# SNAKE_FYP.net
KiCad netlist of a schematic drawn in Altium Designer
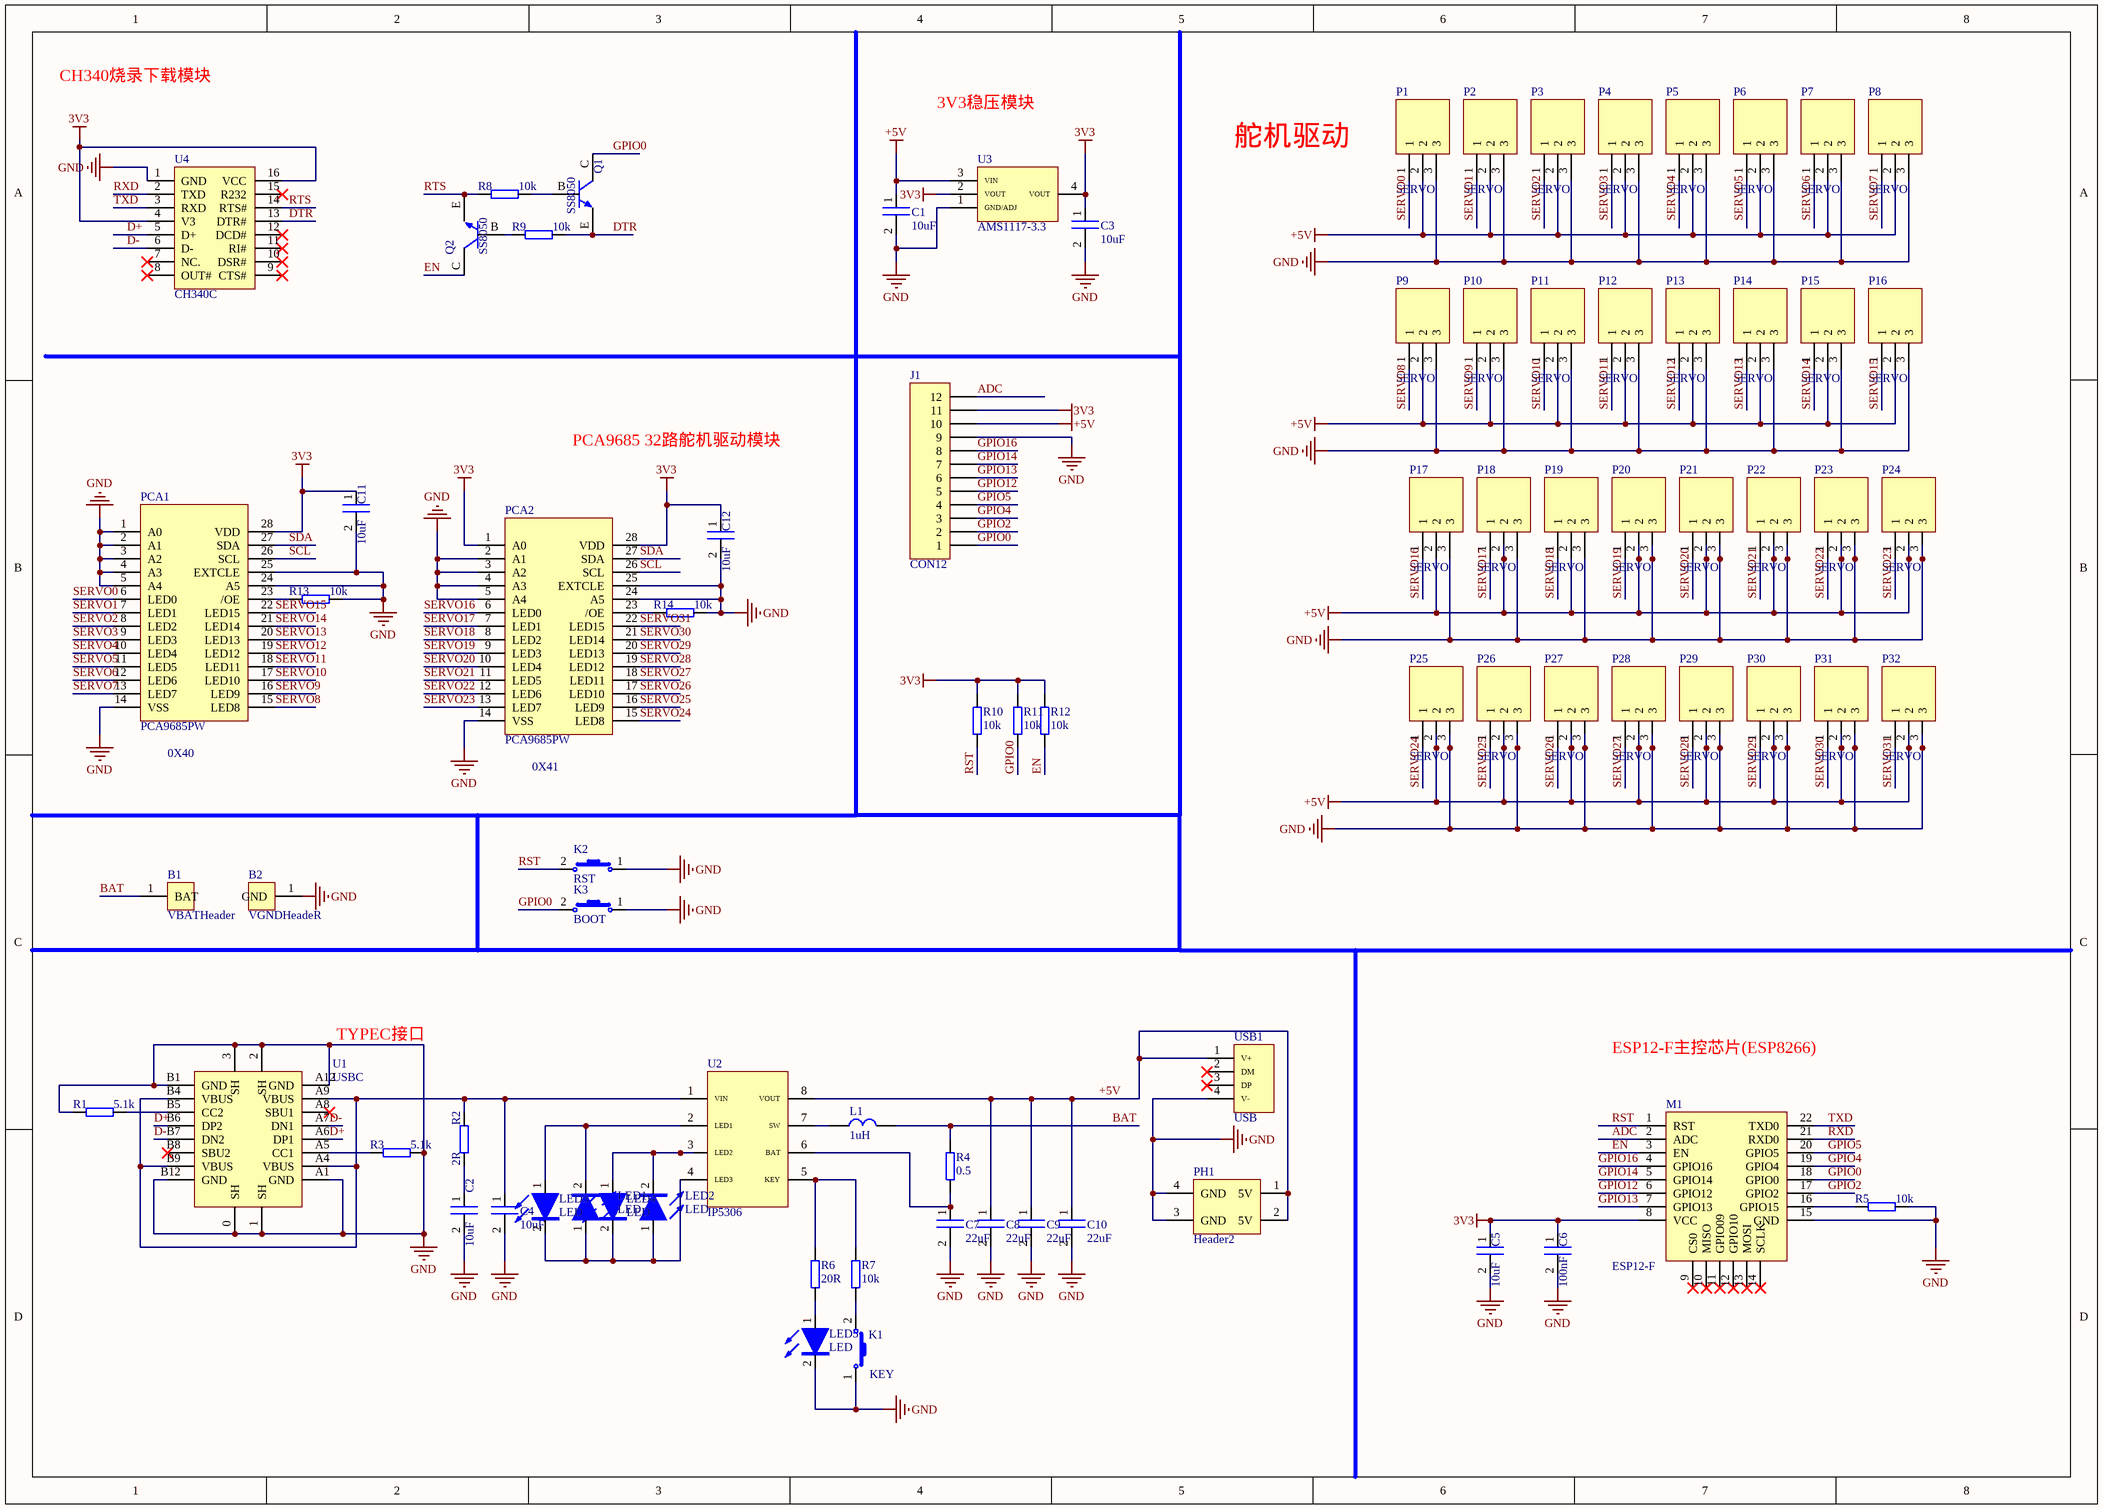
[diagram p0: SNAKE_FYP.SchDoc]

(export (version "E")
  (design (tool "Eeschema 10.0.6"))
  (components
    (comp (ref "B1")
      (value "VBATHeader")
      (footprint "18650VBAT")
      (libsource (lib "SNAKE_FYP") (part "VBATHeader"))
    )
    (comp (ref "B2")
      (value "VGNDHeadeR")
      (footprint "18650GND")
      (libsource (lib "SNAKE_FYP") (part "VGNDHeadeR"))
    )
    (comp (ref "C1")
      (value "10uF")
      (footprint "Cap-0603")
      (description "电容")
      (libsource (lib "Sc") (part "CAP"))
    )
    (comp (ref "C2")
      (value "10uF")
      (footprint "Cap-0603")
      (description "电容")
      (libsource (lib "Sc") (part "CAP"))
    )
    (comp (ref "C3")
      (value "10uF")
      (footprint "Cap-0603")
      (description "电容")
      (libsource (lib "Sc") (part "CAP"))
    )
    (comp (ref "C4")
      (value "10uF")
      (footprint "Cap-0603")
      (description "电容")
      (libsource (lib "Sc") (part "CAP"))
    )
    (comp (ref "C5")
      (value "10uF")
      (footprint "Cap-0603")
      (description "电容")
      (libsource (lib "Sc") (part "CAP"))
    )
    (comp (ref "C6")
      (value "100nF")
      (footprint "Cap-0603")
      (description "电容")
      (libsource (lib "Sc") (part "CAP"))
    )
    (comp (ref "C7")
      (value "22uF")
      (footprint "Cap-0603")
      (description "电容")
      (libsource (lib "Sc") (part "CAP"))
    )
    (comp (ref "C8")
      (value "22uF")
      (footprint "Cap-0603")
      (description "电容")
      (libsource (lib "Sc") (part "CAP"))
    )
    (comp (ref "C9")
      (value "22uF")
      (footprint "Cap-0603")
      (description "电容")
      (libsource (lib "Sc") (part "CAP"))
    )
    (comp (ref "C10")
      (value "22uF")
      (footprint "Cap-0603")
      (description "电容")
      (libsource (lib "Sc") (part "CAP"))
    )
    (comp (ref "C11")
      (value "10uF")
      (footprint "Cap-0603")
      (description "电容")
      (libsource (lib "Sc") (part "CAP"))
    )
    (comp (ref "C12")
      (value "10uF")
      (footprint "Cap-0603")
      (description "电容")
      (libsource (lib "Sc") (part "CAP"))
    )
    (comp (ref "J1")
      (value "CON12")
      (footprint "HDR2X6")
      (description "Connector")
      (libsource (lib "Sc") (part "CON12"))
    )
    (comp (ref "K1")
      (value "KEY")
      (footprint "TSW SMD-3*6*2.5(Button)")
      (description "按键")
      (libsource (lib "Hexapod") (part "RST"))
    )
    (comp (ref "K2")
      (value "RST")
      (footprint "TSW SMD-3*6*2.5(Button)")
      (description "按键")
      (libsource (lib "Sc") (part "RST"))
    )
    (comp (ref "K3")
      (value "BOOT")
      (footprint "TSW SMD-3*6*2.5(Button)")
      (description "按键")
      (libsource (lib "Sc") (part "RST"))
    )
    (comp (ref "L1")
      (value "1uH")
      (footprint "CDRH3D16_4.2*1.8")
      (description "电感")
      (libsource (lib "Hexapod") (part "INDUCTOR"))
    )
    (comp (ref "LED1") (value "LED") (footprint "LED-0805") (libsource (lib "Hexapod") (part "LED")))
    (comp (ref "LED2") (value "LED") (footprint "LED-0805") (libsource (lib "Hexapod") (part "LED")))
    (comp (ref "LED3") (value "LED") (footprint "LED-0805") (libsource (lib "Hexapod") (part "LED")))
    (comp (ref "LED4") (value "LED") (footprint "LED-0805") (libsource (lib "Hexapod") (part "LED")))
    (comp (ref "LED5") (value "LED") (footprint "LED-0805") (libsource (lib "Hexapod") (part "LED")))
    (comp (ref "M1") (value "ESP12-F") (footprint "ESP-12F") (libsource (lib "Sc") (part "ESP12-F")))
    (comp (ref "P1") (value "SERVO") (footprint "SERVOHEADER") (libsource (lib "Sc") (part "SERVO")))
    (comp (ref "P2") (value "SERVO") (footprint "SERVOHEADER") (libsource (lib "Sc") (part "SERVO")))
    (comp (ref "P3") (value "SERVO") (footprint "SERVOHEADER") (libsource (lib "Sc") (part "SERVO")))
    (comp (ref "P4") (value "SERVO") (footprint "SERVOHEADER") (libsource (lib "Sc") (part "SERVO")))
    (comp (ref "P5") (value "SERVO") (footprint "SERVOHEADER") (libsource (lib "Sc") (part "SERVO")))
    (comp (ref "P6") (value "SERVO") (footprint "SERVOHEADER") (libsource (lib "Sc") (part "SERVO")))
    (comp (ref "P7") (value "SERVO") (footprint "SERVOHEADER") (libsource (lib "Sc") (part "SERVO")))
    (comp (ref "P8") (value "SERVO") (footprint "SERVOHEADER") (libsource (lib "Sc") (part "SERVO")))
    (comp (ref "P9") (value "SERVO") (footprint "SERVOHEADER") (libsource (lib "Sc") (part "SERVO")))
    (comp (ref "P10") (value "SERVO") (footprint "SERVOHEADER") (libsource (lib "Sc") (part "SERVO")))
    (comp (ref "P11") (value "SERVO") (footprint "SERVOHEADER") (libsource (lib "Sc") (part "SERVO")))
    (comp (ref "P12") (value "SERVO") (footprint "SERVOHEADER") (libsource (lib "Sc") (part "SERVO")))
    (comp (ref "P13") (value "SERVO") (footprint "SERVOHEADER") (libsource (lib "Sc") (part "SERVO")))
    (comp (ref "P14") (value "SERVO") (footprint "SERVOHEADER") (libsource (lib "Sc") (part "SERVO")))
    (comp (ref "P15") (value "SERVO") (footprint "SERVOHEADER") (libsource (lib "Sc") (part "SERVO")))
    (comp (ref "P16") (value "SERVO") (footprint "SERVOHEADER") (libsource (lib "Sc") (part "SERVO")))
    (comp (ref "P17") (value "SERVO") (footprint "SERVOHEADER") (libsource (lib "Sc") (part "SERVO")))
    (comp (ref "P18") (value "SERVO") (footprint "SERVOHEADER") (libsource (lib "Sc") (part "SERVO")))
    (comp (ref "P19") (value "SERVO") (footprint "SERVOHEADER") (libsource (lib "Sc") (part "SERVO")))
    (comp (ref "P20") (value "SERVO") (footprint "SERVOHEADER") (libsource (lib "Sc") (part "SERVO")))
    (comp (ref "P21") (value "SERVO") (footprint "SERVOHEADER") (libsource (lib "Sc") (part "SERVO")))
    (comp (ref "P22") (value "SERVO") (footprint "SERVOHEADER") (libsource (lib "Sc") (part "SERVO")))
    (comp (ref "P23") (value "SERVO") (footprint "SERVOHEADER") (libsource (lib "Sc") (part "SERVO")))
    (comp (ref "P24") (value "SERVO") (footprint "SERVOHEADER") (libsource (lib "Sc") (part "SERVO")))
    (comp (ref "P25") (value "SERVO") (footprint "SERVOHEADER") (libsource (lib "Sc") (part "SERVO")))
    (comp (ref "P26") (value "SERVO") (footprint "SERVOHEADER") (libsource (lib "Sc") (part "SERVO")))
    (comp (ref "P27") (value "SERVO") (footprint "SERVOHEADER") (libsource (lib "Sc") (part "SERVO")))
    (comp (ref "P28") (value "SERVO") (footprint "SERVOHEADER") (libsource (lib "Sc") (part "SERVO")))
    (comp (ref "P29") (value "SERVO") (footprint "SERVOHEADER") (libsource (lib "Sc") (part "SERVO")))
    (comp (ref "P30") (value "SERVO") (footprint "SERVOHEADER") (libsource (lib "Sc") (part "SERVO")))
    (comp (ref "P31") (value "SERVO") (footprint "SERVOHEADER") (libsource (lib "Sc") (part "SERVO")))
    (comp (ref "P32") (value "SERVO") (footprint "SERVOHEADER") (libsource (lib "Sc") (part "SERVO")))
    (comp (ref "PCA1")
      (value "PCA9685PW")
      (footprint "PCA9685TSOP28")
      (libsource (lib "Sc") (part "PCA9685PW"))
    )
    (comp (ref "PCA2")
      (value "PCA9685PW")
      (footprint "PCA9685TSOP28")
      (libsource (lib "Sc") (part "PCA9685PW"))
    )
    (comp (ref "PH1") (value "Header2") (footprint "HDR2X2") (libsource (lib "ip5306pw") (part "Header2")))
    (comp (ref "Q1") (value "SS8050") (footprint "SOT-23_BEC(SS8050)") (libsource (lib "Sc") (part "SS8050")))
    (comp (ref "Q2") (value "SS8050") (footprint "SOT-23_BEC(SS8050)") (libsource (lib "Sc") (part "SS8050")))
    (comp (ref "R1")
      (value "5.1k")
      (footprint "0603_RES")
      (description "电阻")
      (libsource (lib "Sc") (part "RES"))
    )
    (comp (ref "R2")
      (value "2R")
      (footprint "0603_RES")
      (description "电阻")
      (libsource (lib "Hexapod") (part "RES"))
    )
    (comp (ref "R3")
      (value "5.1k")
      (footprint "0603_RES")
      (description "电阻")
      (libsource (lib "Sc") (part "RES"))
    )
    (comp (ref "R4")
      (value "0.5")
      (footprint "0603_RES")
      (description "电阻")
      (libsource (lib "Hexapod") (part "RES"))
    )
    (comp (ref "R5")
      (value "10k")
      (footprint "0603_RES")
      (description "电阻")
      (libsource (lib "Sc") (part "RES"))
    )
    (comp (ref "R6")
      (value "20R")
      (footprint "0603_RES")
      (description "电阻")
      (libsource (lib "Hexapod") (part "RES"))
    )
    (comp (ref "R7")
      (value "10k")
      (footprint "0603_RES")
      (description "电阻")
      (libsource (lib "Hexapod") (part "RES"))
    )
    (comp (ref "R8")
      (value "10k")
      (footprint "0603_RES")
      (description "电阻")
      (libsource (lib "Sc") (part "RES"))
    )
    (comp (ref "R9")
      (value "10k")
      (footprint "0603_RES")
      (description "电阻")
      (libsource (lib "Sc") (part "RES"))
    )
    (comp (ref "R10")
      (value "10k")
      (footprint "0603_RES")
      (description "电阻")
      (libsource (lib "Sc") (part "RES"))
    )
    (comp (ref "R11")
      (value "10k")
      (footprint "0603_RES")
      (description "电阻")
      (libsource (lib "Sc") (part "RES"))
    )
    (comp (ref "R12")
      (value "10k")
      (footprint "0603_RES")
      (description "电阻")
      (libsource (lib "Sc") (part "RES"))
    )
    (comp (ref "R13")
      (value "10k")
      (footprint "0603_RES")
      (description "电阻")
      (libsource (lib "Sc") (part "RES"))
    )
    (comp (ref "R14")
      (value "10k")
      (footprint "0603_RES")
      (description "电阻")
      (libsource (lib "Sc") (part "RES"))
    )
    (comp (ref "U1") (value "USBC") (footprint "TYPEC") (libsource (lib "ip5306pw") (part "USBC")))
    (comp (ref "U2")
      (value "IP5306")
      (footprint "ESOP_IP5306")
      (description "升压、降压和锂电池充电管理芯片")
      (libsource (lib "ip5306pw") (part "IP5306"))
    )
    (comp (ref "U3")
      (value "AMS1117-3.3")
      (footprint "SOT229P700X180-4N(AMS1117-3.3)")
      (libsource (lib "Sc") (part "AMS1117-3.3"))
    )
    (comp (ref "U4") (value "CH340C") (footprint "SO016_CH340") (libsource (lib "Sc") (part "CH340")))
    (comp (ref "USB1") (value "USB") (footprint "TypeA") (libsource (lib "ip5306pw") (part "USB")))
  )
  (nets
    (net (code "1") (name "+5V") (class "Default")
      (node (ref "C1") (pin "1") (pinfunction "1_1") (pintype "passive"))
      (node (ref "C10") (pin "1") (pinfunction "1_1") (pintype "passive"))
      (node (ref "C8") (pin "1") (pinfunction "1_1") (pintype "passive"))
      (node (ref "C9") (pin "1") (pinfunction "1_1") (pintype "passive"))
      (node (ref "J1") (pin "10") (pinfunction "10_10") (pintype "passive"))
      (node (ref "P1") (pin "2") (pinfunction "2_2") (pintype "passive"))
      (node (ref "P10") (pin "2") (pinfunction "2_2") (pintype "passive"))
      (node (ref "P11") (pin "2") (pinfunction "2_2") (pintype "passive"))
      (node (ref "P12") (pin "2") (pinfunction "2_2") (pintype "passive"))
      (node (ref "P13") (pin "2") (pinfunction "2_2") (pintype "passive"))
      (node (ref "P14") (pin "2") (pinfunction "2_2") (pintype "passive"))
      (node (ref "P15") (pin "2") (pinfunction "2_2") (pintype "passive"))
      (node (ref "P16") (pin "2") (pinfunction "2_2") (pintype "passive"))
      (node (ref "P17") (pin "2") (pinfunction "2_2") (pintype "passive"))
      (node (ref "P18") (pin "2") (pinfunction "2_2") (pintype "passive"))
      (node (ref "P19") (pin "2") (pinfunction "2_2") (pintype "passive"))
      (node (ref "P2") (pin "2") (pinfunction "2_2") (pintype "passive"))
      (node (ref "P20") (pin "2") (pinfunction "2_2") (pintype "passive"))
      (node (ref "P21") (pin "2") (pinfunction "2_2") (pintype "passive"))
      (node (ref "P22") (pin "2") (pinfunction "2_2") (pintype "passive"))
      (node (ref "P23") (pin "2") (pinfunction "2_2") (pintype "passive"))
      (node (ref "P24") (pin "2") (pinfunction "2_2") (pintype "passive"))
      (node (ref "P25") (pin "2") (pinfunction "2_2") (pintype "passive"))
      (node (ref "P26") (pin "2") (pinfunction "2_2") (pintype "passive"))
      (node (ref "P27") (pin "2") (pinfunction "2_2") (pintype "passive"))
      (node (ref "P28") (pin "2") (pinfunction "2_2") (pintype "passive"))
      (node (ref "P29") (pin "2") (pinfunction "2_2") (pintype "passive"))
      (node (ref "P3") (pin "2") (pinfunction "2_2") (pintype "passive"))
      (node (ref "P30") (pin "2") (pinfunction "2_2") (pintype "passive"))
      (node (ref "P31") (pin "2") (pinfunction "2_2") (pintype "passive"))
      (node (ref "P32") (pin "2") (pinfunction "2_2") (pintype "passive"))
      (node (ref "P4") (pin "2") (pinfunction "2_2") (pintype "passive"))
      (node (ref "P5") (pin "2") (pinfunction "2_2") (pintype "passive"))
      (node (ref "P6") (pin "2") (pinfunction "2_2") (pintype "passive"))
      (node (ref "P7") (pin "2") (pinfunction "2_2") (pintype "passive"))
      (node (ref "P8") (pin "2") (pinfunction "2_2") (pintype "passive"))
      (node (ref "P9") (pin "2") (pinfunction "2_2") (pintype "passive"))
      (node (ref "PH1") (pin "1") (pinfunction "5V_1") (pintype "passive"))
      (node (ref "PH1") (pin "2") (pinfunction "5V_2") (pintype "passive"))
      (node (ref "U2") (pin "8") (pinfunction "VOUT_8") (pintype "passive"))
      (node (ref "U3") (pin "3") (pinfunction "VIN_3") (pintype "passive"))
      (node (ref "USB1") (pin "1") (pinfunction "V+_1") (pintype "passive"))
    )
    (net (code "2") (name "/ADC") (class "Default")
      (node (ref "J1") (pin "12") (pinfunction "12_12") (pintype "passive"))
      (node (ref "M1") (pin "2") (pinfunction "ADC_2") (pintype "passive"))
    )
    (net (code "3") (name "/BAT") (class "Default")
      (node (ref "B1") (pin "1") (pinfunction "BAT_1") (pintype "passive"))
      (node (ref "L1") (pin "2") (pinfunction "2_2") (pintype "passive"))
      (node (ref "R4") (pin "2") (pinfunction "2_2") (pintype "passive"))
    )
    (net (code "4") (name "/D+") (class "Default")
      (node (ref "U1") (pin "A6") (pinfunction "DP1_A6") (pintype "passive"))
      (node (ref "U1") (pin "B6") (pinfunction "DP2_B6") (pintype "passive"))
      (node (ref "U4") (pin "5") (pinfunction "D+_5") (pintype "passive"))
    )
    (net (code "5") (name "/D-") (class "Default")
      (node (ref "U1") (pin "A7") (pinfunction "DN1_A7") (pintype "passive"))
      (node (ref "U1") (pin "B7") (pinfunction "DN2_B7") (pintype "passive"))
      (node (ref "U4") (pin "6") (pinfunction "D-_6") (pintype "passive"))
    )
    (net (code "6") (name "/DTR") (class "Default")
      (node (ref "Q1") (pin "E") (pinfunction "3_E") (pintype "passive"))
      (node (ref "R9") (pin "2") (pinfunction "2_2") (pintype "passive"))
      (node (ref "U4") (pin "13") (pinfunction "DTR#_13") (pintype "passive"))
    )
    (net (code "7") (name "/EN") (class "Default")
      (node (ref "M1") (pin "3") (pinfunction "EN_3") (pintype "passive"))
      (node (ref "Q2") (pin "C") (pinfunction "1_C") (pintype "passive"))
      (node (ref "R12") (pin "2") (pinfunction "2_2") (pintype "passive"))
    )
    (net (code "8") (name "/GPIO0") (class "Default")
      (node (ref "J1") (pin "1") (pinfunction "1_1") (pintype "passive"))
      (node (ref "K3") (pin "2") (pinfunction "2_2") (pintype "passive"))
      (node (ref "M1") (pin "18") (pinfunction "GPIO0_18") (pintype "passive"))
      (node (ref "Q1") (pin "C") (pinfunction "1_C") (pintype "passive"))
      (node (ref "R11") (pin "2") (pinfunction "2_2") (pintype "passive"))
    )
    (net (code "9") (name "/GPIO2") (class "Default")
      (node (ref "J1") (pin "2") (pinfunction "2_2") (pintype "passive"))
      (node (ref "M1") (pin "17") (pinfunction "GPIO2_17") (pintype "passive"))
    )
    (net (code "10") (name "/GPIO4") (class "Default")
      (node (ref "J1") (pin "3") (pinfunction "3_3") (pintype "passive"))
      (node (ref "M1") (pin "19") (pinfunction "GPIO4_19") (pintype "passive"))
    )
    (net (code "11") (name "/GPIO5") (class "Default")
      (node (ref "J1") (pin "4") (pinfunction "4_4") (pintype "passive"))
      (node (ref "M1") (pin "20") (pinfunction "GPIO5_20") (pintype "passive"))
    )
    (net (code "12") (name "/GPIO12") (class "Default")
      (node (ref "J1") (pin "5") (pinfunction "5_5") (pintype "passive"))
      (node (ref "M1") (pin "6") (pinfunction "GPIO12_6") (pintype "passive"))
    )
    (net (code "13") (name "/GPIO13") (class "Default")
      (node (ref "J1") (pin "6") (pinfunction "6_6") (pintype "passive"))
      (node (ref "M1") (pin "7") (pinfunction "GPIO13_7") (pintype "passive"))
    )
    (net (code "14") (name "/GPIO14") (class "Default")
      (node (ref "J1") (pin "7") (pinfunction "7_7") (pintype "passive"))
      (node (ref "M1") (pin "5") (pinfunction "GPIO14_5") (pintype "passive"))
    )
    (net (code "15") (name "/GPIO16") (class "Default")
      (node (ref "J1") (pin "8") (pinfunction "8_8") (pintype "passive"))
      (node (ref "M1") (pin "4") (pinfunction "GPIO16_4") (pintype "passive"))
    )
    (net (code "16") (name "/RST") (class "Default")
      (node (ref "K2") (pin "2") (pinfunction "2_2") (pintype "passive"))
      (node (ref "M1") (pin "1") (pinfunction "RST_1") (pintype "passive"))
      (node (ref "R10") (pin "2") (pinfunction "2_2") (pintype "passive"))
    )
    (net (code "17") (name "/RTS") (class "Default")
      (node (ref "Q2") (pin "E") (pinfunction "3_E") (pintype "passive"))
      (node (ref "R8") (pin "1") (pinfunction "1_1") (pintype "passive"))
      (node (ref "U4") (pin "14") (pinfunction "RTS#_14") (pintype "passive"))
    )
    (net (code "18") (name "/RXD") (class "Default")
      (node (ref "M1") (pin "21") (pinfunction "RXD0_21") (pintype "passive"))
      (node (ref "U4") (pin "2") (pinfunction "TXD_2") (pintype "passive"))
    )
    (net (code "19") (name "/SCL") (class "Default")
      (node (ref "PCA1") (pin "26") (pinfunction "SCL_26") (pintype "passive"))
      (node (ref "PCA2") (pin "26") (pinfunction "SCL_26") (pintype "passive"))
    )
    (net (code "20") (name "/SDA") (class "Default")
      (node (ref "PCA1") (pin "27") (pinfunction "SDA_27") (pintype "passive"))
      (node (ref "PCA2") (pin "27") (pinfunction "SDA_27") (pintype "passive"))
    )
    (net (code "21") (name "/SERVO0") (class "Default")
      (node (ref "P1") (pin "1") (pinfunction "1_1") (pintype "passive"))
      (node (ref "PCA1") (pin "6") (pinfunction "LED0_6") (pintype "passive"))
    )
    (net (code "22") (name "/SERVO1") (class "Default")
      (node (ref "P2") (pin "1") (pinfunction "1_1") (pintype "passive"))
      (node (ref "PCA1") (pin "7") (pinfunction "LED1_7") (pintype "passive"))
    )
    (net (code "23") (name "/SERVO2") (class "Default")
      (node (ref "P3") (pin "1") (pinfunction "1_1") (pintype "passive"))
      (node (ref "PCA1") (pin "8") (pinfunction "LED2_8") (pintype "passive"))
    )
    (net (code "24") (name "/SERVO3") (class "Default")
      (node (ref "P4") (pin "1") (pinfunction "1_1") (pintype "passive"))
      (node (ref "PCA1") (pin "9") (pinfunction "LED3_9") (pintype "passive"))
    )
    (net (code "25") (name "/SERVO4") (class "Default")
      (node (ref "P5") (pin "1") (pinfunction "1_1") (pintype "passive"))
      (node (ref "PCA1") (pin "10") (pinfunction "LED4_10") (pintype "passive"))
    )
    (net (code "26") (name "/SERVO5") (class "Default")
      (node (ref "P6") (pin "1") (pinfunction "1_1") (pintype "passive"))
      (node (ref "PCA1") (pin "11") (pinfunction "LED5_11") (pintype "passive"))
    )
    (net (code "27") (name "/SERVO6") (class "Default")
      (node (ref "P7") (pin "1") (pinfunction "1_1") (pintype "passive"))
      (node (ref "PCA1") (pin "12") (pinfunction "LED6_12") (pintype "passive"))
    )
    (net (code "28") (name "/SERVO7") (class "Default")
      (node (ref "P8") (pin "1") (pinfunction "1_1") (pintype "passive"))
      (node (ref "PCA1") (pin "13") (pinfunction "LED7_13") (pintype "passive"))
    )
    (net (code "29") (name "/SERVO8") (class "Default")
      (node (ref "P9") (pin "1") (pinfunction "1_1") (pintype "passive"))
      (node (ref "PCA1") (pin "15") (pinfunction "LED8_15") (pintype "passive"))
    )
    (net (code "30") (name "/SERVO9") (class "Default")
      (node (ref "P10") (pin "1") (pinfunction "1_1") (pintype "passive"))
      (node (ref "PCA1") (pin "16") (pinfunction "LED9_16") (pintype "passive"))
    )
    (net (code "31") (name "/SERVO10") (class "Default")
      (node (ref "P11") (pin "1") (pinfunction "1_1") (pintype "passive"))
      (node (ref "PCA1") (pin "17") (pinfunction "LED10_17") (pintype "passive"))
    )
    (net (code "32") (name "/SERVO11") (class "Default")
      (node (ref "P12") (pin "1") (pinfunction "1_1") (pintype "passive"))
      (node (ref "PCA1") (pin "18") (pinfunction "LED11_18") (pintype "passive"))
    )
    (net (code "33") (name "/SERVO12") (class "Default")
      (node (ref "P13") (pin "1") (pinfunction "1_1") (pintype "passive"))
      (node (ref "PCA1") (pin "19") (pinfunction "LED12_19") (pintype "passive"))
    )
    (net (code "34") (name "/SERVO13") (class "Default")
      (node (ref "P14") (pin "1") (pinfunction "1_1") (pintype "passive"))
      (node (ref "PCA1") (pin "20") (pinfunction "LED13_20") (pintype "passive"))
    )
    (net (code "35") (name "/SERVO14") (class "Default")
      (node (ref "P15") (pin "1") (pinfunction "1_1") (pintype "passive"))
      (node (ref "PCA1") (pin "21") (pinfunction "LED14_21") (pintype "passive"))
    )
    (net (code "36") (name "/SERVO15") (class "Default")
      (node (ref "P16") (pin "1") (pinfunction "1_1") (pintype "passive"))
      (node (ref "PCA1") (pin "22") (pinfunction "LED15_22") (pintype "passive"))
    )
    (net (code "37") (name "/SERVO16") (class "Default")
      (node (ref "P17") (pin "1") (pinfunction "1_1") (pintype "passive"))
      (node (ref "PCA2") (pin "6") (pinfunction "LED0_6") (pintype "passive"))
    )
    (net (code "38") (name "/SERVO17") (class "Default")
      (node (ref "P18") (pin "1") (pinfunction "1_1") (pintype "passive"))
      (node (ref "PCA2") (pin "7") (pinfunction "LED1_7") (pintype "passive"))
    )
    (net (code "39") (name "/SERVO18") (class "Default")
      (node (ref "P19") (pin "1") (pinfunction "1_1") (pintype "passive"))
      (node (ref "PCA2") (pin "8") (pinfunction "LED2_8") (pintype "passive"))
    )
    (net (code "40") (name "/SERVO19") (class "Default")
      (node (ref "P20") (pin "1") (pinfunction "1_1") (pintype "passive"))
      (node (ref "PCA2") (pin "9") (pinfunction "LED3_9") (pintype "passive"))
    )
    (net (code "41") (name "/SERVO20") (class "Default")
      (node (ref "P21") (pin "1") (pinfunction "1_1") (pintype "passive"))
      (node (ref "PCA2") (pin "10") (pinfunction "LED4_10") (pintype "passive"))
    )
    (net (code "42") (name "/SERVO21") (class "Default")
      (node (ref "P22") (pin "1") (pinfunction "1_1") (pintype "passive"))
      (node (ref "PCA2") (pin "11") (pinfunction "LED5_11") (pintype "passive"))
    )
    (net (code "43") (name "/SERVO22") (class "Default")
      (node (ref "P23") (pin "1") (pinfunction "1_1") (pintype "passive"))
      (node (ref "PCA2") (pin "12") (pinfunction "LED6_12") (pintype "passive"))
    )
    (net (code "44") (name "/SERVO23") (class "Default")
      (node (ref "P24") (pin "1") (pinfunction "1_1") (pintype "passive"))
      (node (ref "PCA2") (pin "13") (pinfunction "LED7_13") (pintype "passive"))
    )
    (net (code "45") (name "/SERVO24") (class "Default")
      (node (ref "P25") (pin "1") (pinfunction "1_1") (pintype "passive"))
      (node (ref "PCA2") (pin "15") (pinfunction "LED8_15") (pintype "passive"))
    )
    (net (code "46") (name "/SERVO25") (class "Default")
      (node (ref "P26") (pin "1") (pinfunction "1_1") (pintype "passive"))
      (node (ref "PCA2") (pin "16") (pinfunction "LED9_16") (pintype "passive"))
    )
    (net (code "47") (name "/SERVO26") (class "Default")
      (node (ref "P27") (pin "1") (pinfunction "1_1") (pintype "passive"))
      (node (ref "PCA2") (pin "17") (pinfunction "LED10_17") (pintype "passive"))
    )
    (net (code "48") (name "/SERVO27") (class "Default")
      (node (ref "P28") (pin "1") (pinfunction "1_1") (pintype "passive"))
      (node (ref "PCA2") (pin "18") (pinfunction "LED11_18") (pintype "passive"))
    )
    (net (code "49") (name "/SERVO28") (class "Default")
      (node (ref "P29") (pin "1") (pinfunction "1_1") (pintype "passive"))
      (node (ref "PCA2") (pin "19") (pinfunction "LED12_19") (pintype "passive"))
    )
    (net (code "50") (name "/SERVO29") (class "Default")
      (node (ref "P30") (pin "1") (pinfunction "1_1") (pintype "passive"))
      (node (ref "PCA2") (pin "20") (pinfunction "LED13_20") (pintype "passive"))
    )
    (net (code "51") (name "/SERVO30") (class "Default")
      (node (ref "P31") (pin "1") (pinfunction "1_1") (pintype "passive"))
      (node (ref "PCA2") (pin "21") (pinfunction "LED14_21") (pintype "passive"))
    )
    (net (code "52") (name "/SERVO31") (class "Default")
      (node (ref "P32") (pin "1") (pinfunction "1_1") (pintype "passive"))
      (node (ref "PCA2") (pin "22") (pinfunction "LED15_22") (pintype "passive"))
    )
    (net (code "53") (name "/TXD") (class "Default")
      (node (ref "M1") (pin "22") (pinfunction "TXD0_22") (pintype "passive"))
      (node (ref "U4") (pin "3") (pinfunction "RXD_3") (pintype "passive"))
    )
    (net (code "54") (name "3V3") (class "Default")
      (node (ref "C11") (pin "1") (pinfunction "1_1") (pintype "passive"))
      (node (ref "C12") (pin "1") (pinfunction "1_1") (pintype "passive"))
      (node (ref "C3") (pin "1") (pinfunction "1_1") (pintype "passive"))
      (node (ref "C5") (pin "1") (pinfunction "1_1") (pintype "passive"))
      (node (ref "C6") (pin "1") (pinfunction "1_1") (pintype "passive"))
      (node (ref "J1") (pin "11") (pinfunction "11_11") (pintype "passive"))
      (node (ref "M1") (pin "8") (pinfunction "VCC_8") (pintype "passive"))
      (node (ref "PCA1") (pin "28") (pinfunction "VDD_28") (pintype "passive"))
      (node (ref "PCA2") (pin "1") (pinfunction "A0_1") (pintype "passive"))
      (node (ref "PCA2") (pin "28") (pinfunction "VDD_28") (pintype "passive"))
      (node (ref "R10") (pin "1") (pinfunction "1_1") (pintype "passive"))
      (node (ref "R11") (pin "1") (pinfunction "1_1") (pintype "passive"))
      (node (ref "R12") (pin "1") (pinfunction "1_1") (pintype "passive"))
      (node (ref "U3") (pin "2") (pinfunction "VOUT_2") (pintype "passive"))
      (node (ref "U3") (pin "4") (pinfunction "VOUT_4") (pintype "passive"))
      (node (ref "U4") (pin "16") (pinfunction "VCC_16") (pintype "passive"))
      (node (ref "U4") (pin "4") (pinfunction "V3_4") (pintype "passive"))
    )
    (net (code "55") (name "GND") (class "Default")
      (node (ref "B2") (pin "1") (pinfunction "GND_1") (pintype "passive"))
      (node (ref "C1") (pin "2") (pinfunction "2_2") (pintype "passive"))
      (node (ref "C10") (pin "2") (pinfunction "2_2") (pintype "passive"))
      (node (ref "C11") (pin "2") (pinfunction "2_2") (pintype "passive"))
      (node (ref "C12") (pin "2") (pinfunction "2_2") (pintype "passive"))
      (node (ref "C2") (pin "2") (pinfunction "2_2") (pintype "passive"))
      (node (ref "C3") (pin "2") (pinfunction "2_2") (pintype "passive"))
      (node (ref "C4") (pin "2") (pinfunction "2_2") (pintype "passive"))
      (node (ref "C5") (pin "2") (pinfunction "2_2") (pintype "passive"))
      (node (ref "C6") (pin "2") (pinfunction "2_2") (pintype "passive"))
      (node (ref "C7") (pin "2") (pinfunction "2_2") (pintype "passive"))
      (node (ref "C8") (pin "2") (pinfunction "2_2") (pintype "passive"))
      (node (ref "C9") (pin "2") (pinfunction "2_2") (pintype "passive"))
      (node (ref "J1") (pin "9") (pinfunction "9_9") (pintype "passive"))
      (node (ref "K1") (pin "1") (pinfunction "1_1") (pintype "passive"))
      (node (ref "K2") (pin "1") (pinfunction "1_1") (pintype "passive"))
      (node (ref "K3") (pin "1") (pinfunction "1_1") (pintype "passive"))
      (node (ref "LED5") (pin "2") (pinfunction "2_2") (pintype "passive"))
      (node (ref "M1") (pin "15") (pinfunction "GND_15") (pintype "passive"))
      (node (ref "P1") (pin "3") (pinfunction "3_3") (pintype "passive"))
      (node (ref "P10") (pin "3") (pinfunction "3_3") (pintype "passive"))
      (node (ref "P11") (pin "3") (pinfunction "3_3") (pintype "passive"))
      (node (ref "P12") (pin "3") (pinfunction "3_3") (pintype "passive"))
      (node (ref "P13") (pin "3") (pinfunction "3_3") (pintype "passive"))
      (node (ref "P14") (pin "3") (pinfunction "3_3") (pintype "passive"))
      (node (ref "P15") (pin "3") (pinfunction "3_3") (pintype "passive"))
      (node (ref "P16") (pin "3") (pinfunction "3_3") (pintype "passive"))
      (node (ref "P17") (pin "3") (pinfunction "3_3") (pintype "passive"))
      (node (ref "P18") (pin "3") (pinfunction "3_3") (pintype "passive"))
      (node (ref "P19") (pin "3") (pinfunction "3_3") (pintype "passive"))
      (node (ref "P2") (pin "3") (pinfunction "3_3") (pintype "passive"))
      (node (ref "P20") (pin "3") (pinfunction "3_3") (pintype "passive"))
      (node (ref "P21") (pin "3") (pinfunction "3_3") (pintype "passive"))
      (node (ref "P22") (pin "3") (pinfunction "3_3") (pintype "passive"))
      (node (ref "P23") (pin "3") (pinfunction "3_3") (pintype "passive"))
      (node (ref "P24") (pin "3") (pinfunction "3_3") (pintype "passive"))
      (node (ref "P25") (pin "3") (pinfunction "3_3") (pintype "passive"))
      (node (ref "P26") (pin "3") (pinfunction "3_3") (pintype "passive"))
      (node (ref "P27") (pin "3") (pinfunction "3_3") (pintype "passive"))
      (node (ref "P28") (pin "3") (pinfunction "3_3") (pintype "passive"))
      (node (ref "P29") (pin "3") (pinfunction "3_3") (pintype "passive"))
      (node (ref "P3") (pin "3") (pinfunction "3_3") (pintype "passive"))
      (node (ref "P30") (pin "3") (pinfunction "3_3") (pintype "passive"))
      (node (ref "P31") (pin "3") (pinfunction "3_3") (pintype "passive"))
      (node (ref "P32") (pin "3") (pinfunction "3_3") (pintype "passive"))
      (node (ref "P4") (pin "3") (pinfunction "3_3") (pintype "passive"))
      (node (ref "P5") (pin "3") (pinfunction "3_3") (pintype "passive"))
      (node (ref "P6") (pin "3") (pinfunction "3_3") (pintype "passive"))
      (node (ref "P7") (pin "3") (pinfunction "3_3") (pintype "passive"))
      (node (ref "P8") (pin "3") (pinfunction "3_3") (pintype "passive"))
      (node (ref "P9") (pin "3") (pinfunction "3_3") (pintype "passive"))
      (node (ref "PCA1") (pin "1") (pinfunction "A0_1") (pintype "passive"))
      (node (ref "PCA1") (pin "14") (pinfunction "VSS_14") (pintype "passive"))
      (node (ref "PCA1") (pin "2") (pinfunction "A1_2") (pintype "passive"))
      (node (ref "PCA1") (pin "24") (pinfunction "A5_24") (pintype "passive"))
      (node (ref "PCA1") (pin "25") (pinfunction "EXTCLE_25") (pintype "passive"))
      (node (ref "PCA1") (pin "3") (pinfunction "A2_3") (pintype "passive"))
      (node (ref "PCA1") (pin "4") (pinfunction "A3_4") (pintype "passive"))
      (node (ref "PCA1") (pin "5") (pinfunction "A4_5") (pintype "passive"))
      (node (ref "PCA2") (pin "14") (pinfunction "VSS_14") (pintype "passive"))
      (node (ref "PCA2") (pin "2") (pinfunction "A1_2") (pintype "passive"))
      (node (ref "PCA2") (pin "24") (pinfunction "A5_24") (pintype "passive"))
      (node (ref "PCA2") (pin "25") (pinfunction "EXTCLE_25") (pintype "passive"))
      (node (ref "PCA2") (pin "3") (pinfunction "A2_3") (pintype "passive"))
      (node (ref "PCA2") (pin "4") (pinfunction "A3_4") (pintype "passive"))
      (node (ref "PCA2") (pin "5") (pinfunction "A4_5") (pintype "passive"))
      (node (ref "PH1") (pin "3") (pinfunction "GND_3") (pintype "passive"))
      (node (ref "PH1") (pin "4") (pinfunction "GND_4") (pintype "passive"))
      (node (ref "R1") (pin "1") (pinfunction "1_1") (pintype "passive"))
      (node (ref "R13") (pin "2") (pinfunction "2_2") (pintype "passive"))
      (node (ref "R14") (pin "2") (pinfunction "2_2") (pintype "passive"))
      (node (ref "R3") (pin "2") (pinfunction "2_2") (pintype "passive"))
      (node (ref "R5") (pin "2") (pinfunction "2_2") (pintype "passive"))
      (node (ref "U1") (pin "0") (pinfunction "SH_0") (pintype "passive"))
      (node (ref "U1") (pin "1") (pinfunction "SH_1") (pintype "passive"))
      (node (ref "U1") (pin "2") (pinfunction "SH_2") (pintype "passive"))
      (node (ref "U1") (pin "3") (pinfunction "SH_3") (pintype "passive"))
      (node (ref "U1") (pin "A1") (pinfunction "GND_A1") (pintype "passive"))
      (node (ref "U1") (pin "A12") (pinfunction "GND_A12") (pintype "passive"))
      (node (ref "U1") (pin "B1") (pinfunction "GND_B1") (pintype "passive"))
      (node (ref "U1") (pin "B12") (pinfunction "GND_B12") (pintype "passive"))
      (node (ref "U3") (pin "1") (pinfunction "GND/ADJ_1") (pintype "passive"))
      (node (ref "U4") (pin "1") (pinfunction "GND_1") (pintype "passive"))
      (node (ref "USB1") (pin "4") (pinfunction "V-_4") (pintype "passive"))
    )
    (net (code "56") (name "Net-(C2-Pad1)") (class "Default")
      (node (ref "C2") (pin "1") (pinfunction "1_1") (pintype "passive"))
      (node (ref "R2") (pin "1") (pinfunction "1_1") (pintype "passive"))
    )
    (net (code "57") (name "Net-(K1-Pad2)") (class "Default")
      (node (ref "K1") (pin "2") (pinfunction "2_2") (pintype "passive"))
      (node (ref "R7") (pin "2") (pinfunction "2_2") (pintype "passive"))
    )
    (net (code "58") (name "Net-(LED5-Pad1)") (class "Default")
      (node (ref "LED5") (pin "1") (pinfunction "1_1") (pintype "passive"))
      (node (ref "R6") (pin "2") (pinfunction "2_2") (pintype "passive"))
    )
    (net (code "59") (name "Net-(M1-GPIO15)") (class "Default")
      (node (ref "M1") (pin "16") (pinfunction "GPIO15_16") (pintype "passive"))
      (node (ref "R5") (pin "1") (pinfunction "1_1") (pintype "passive"))
    )
    (net (code "60") (name "Net-(PCA1-{slash}OE)") (class "Default")
      (node (ref "PCA1") (pin "23") (pinfunction "/OE_23") (pintype "passive"))
      (node (ref "R13") (pin "1") (pinfunction "1_1") (pintype "passive"))
    )
    (net (code "61") (name "Net-(PCA2-{slash}OE)") (class "Default")
      (node (ref "PCA2") (pin "23") (pinfunction "/OE_23") (pintype "passive"))
      (node (ref "R14") (pin "1") (pinfunction "1_1") (pintype "passive"))
    )
    (net (code "62") (name "Net-(Q1-2)") (class "Default")
      (node (ref "Q1") (pin "B") (pinfunction "2_B") (pintype "passive"))
      (node (ref "R8") (pin "2") (pinfunction "2_2") (pintype "passive"))
    )
    (net (code "63") (name "Net-(Q2-2)") (class "Default")
      (node (ref "Q2") (pin "B") (pinfunction "2_B") (pintype "passive"))
      (node (ref "R9") (pin "1") (pinfunction "1_1") (pintype "passive"))
    )
    (net (code "64") (name "Net-(U1-CC1)") (class "Default")
      (node (ref "R3") (pin "1") (pinfunction "1_1") (pintype "passive"))
      (node (ref "U1") (pin "A5") (pinfunction "CC1_A5") (pintype "passive"))
    )
    (net (code "65") (name "Net-(U1-CC2)") (class "Default")
      (node (ref "R1") (pin "2") (pinfunction "2_2") (pintype "passive"))
      (node (ref "U1") (pin "B5") (pinfunction "CC2_B5") (pintype "passive"))
    )
    (net (code "66") (name "Net-(U2-BAT)") (class "Default")
      (node (ref "C7") (pin "1") (pinfunction "1_1") (pintype "passive"))
      (node (ref "R4") (pin "1") (pinfunction "1_1") (pintype "passive"))
      (node (ref "U2") (pin "6") (pinfunction "BAT_6") (pintype "passive"))
    )
    (net (code "67") (name "Net-(U2-KEY)") (class "Default")
      (node (ref "R6") (pin "1") (pinfunction "1_1") (pintype "passive"))
      (node (ref "R7") (pin "1") (pinfunction "1_1") (pintype "passive"))
      (node (ref "U2") (pin "5") (pinfunction "KEY_5") (pintype "passive"))
    )
    (net (code "68") (name "Net-(U2-LED1)") (class "Default")
      (node (ref "LED1") (pin "2") (pinfunction "2_2") (pintype "passive"))
      (node (ref "LED3") (pin "1") (pinfunction "1_1") (pintype "passive"))
      (node (ref "U2") (pin "2") (pinfunction "LED1_2") (pintype "passive"))
    )
    (net (code "69") (name "Net-(U2-LED2)") (class "Default")
      (node (ref "LED2") (pin "2") (pinfunction "2_2") (pintype "passive"))
      (node (ref "LED4") (pin "1") (pinfunction "1_1") (pintype "passive"))
      (node (ref "U2") (pin "3") (pinfunction "LED2_3") (pintype "passive"))
    )
    (net (code "70") (name "Net-(U2-LED3)") (class "Default")
      (node (ref "LED1") (pin "1") (pinfunction "1_1") (pintype "passive"))
      (node (ref "LED2") (pin "1") (pinfunction "1_1") (pintype "passive"))
      (node (ref "LED3") (pin "2") (pinfunction "2_2") (pintype "passive"))
      (node (ref "LED4") (pin "2") (pinfunction "2_2") (pintype "passive"))
      (node (ref "U2") (pin "4") (pinfunction "LED3_4") (pintype "passive"))
    )
    (net (code "71") (name "Net-(U2-SW)") (class "Default")
      (node (ref "L1") (pin "1") (pinfunction "1_1") (pintype "passive"))
      (node (ref "U2") (pin "7") (pinfunction "SW_7") (pintype "passive"))
    )
    (net (code "72") (name "Net-(U2-VIN)") (class "Default")
      (node (ref "C4") (pin "1") (pinfunction "1_1") (pintype "passive"))
      (node (ref "R2") (pin "2") (pinfunction "2_2") (pintype "passive"))
      (node (ref "U1") (pin "A4") (pinfunction "VBUS_A4") (pintype "passive"))
      (node (ref "U1") (pin "A9") (pinfunction "VBUS_A9") (pintype "passive"))
      (node (ref "U1") (pin "B4") (pinfunction "VBUS_B4") (pintype "passive"))
      (node (ref "U1") (pin "B9") (pinfunction "VBUS_B9") (pintype "passive"))
      (node (ref "U2") (pin "1") (pinfunction "VIN_1") (pintype "passive"))
    )
    (net (code "73") (name "unconnected-(M1-CS0-Pad9)") (class "Default")
      (node (ref "M1") (pin "9") (pinfunction "CS0_9") (pintype "passive+no_connect"))
    )
    (net (code "74") (name "unconnected-(M1-GPIO09-Pad11)") (class "Default")
      (node (ref "M1") (pin "11") (pinfunction "GPIO09_11") (pintype "passive+no_connect"))
    )
    (net (code "75") (name "unconnected-(M1-GPIO10-Pad12)") (class "Default")
      (node (ref "M1") (pin "12") (pinfunction "GPIO10_12") (pintype "passive+no_connect"))
    )
    (net (code "76") (name "unconnected-(M1-MISO-Pad10)") (class "Default")
      (node (ref "M1") (pin "10") (pinfunction "MISO_10") (pintype "passive+no_connect"))
    )
    (net (code "77") (name "unconnected-(M1-MOSI-Pad13)") (class "Default")
      (node (ref "M1") (pin "13") (pinfunction "MOSI_13") (pintype "passive+no_connect"))
    )
    (net (code "78") (name "unconnected-(M1-SCLK-Pad14)") (class "Default")
      (node (ref "M1") (pin "14") (pinfunction "SCLK_14") (pintype "passive+no_connect"))
    )
    (net (code "79") (name "unconnected-(U1-SBU1-PadA8)") (class "Default")
      (node (ref "U1") (pin "A8") (pinfunction "SBU1_A8") (pintype "passive+no_connect"))
    )
    (net (code "80") (name "unconnected-(U1-SBU2-PadB8)") (class "Default")
      (node (ref "U1") (pin "B8") (pinfunction "SBU2_B8") (pintype "passive+no_connect"))
    )
    (net (code "81") (name "unconnected-(U4-CTS#-Pad9)") (class "Default")
      (node (ref "U4") (pin "9") (pinfunction "CTS#_9") (pintype "passive+no_connect"))
    )
    (net (code "82") (name "unconnected-(U4-DCD#-Pad12)") (class "Default")
      (node (ref "U4") (pin "12") (pinfunction "DCD#_12") (pintype "passive+no_connect"))
    )
    (net (code "83") (name "unconnected-(U4-DSR#-Pad10)") (class "Default")
      (node (ref "U4") (pin "10") (pinfunction "DSR#_10") (pintype "passive+no_connect"))
    )
    (net (code "84") (name "unconnected-(U4-NC.-Pad7)") (class "Default")
      (node (ref "U4") (pin "7") (pinfunction "NC._7") (pintype "passive+no_connect"))
    )
    (net (code "85") (name "unconnected-(U4-OUT#-Pad8)") (class "Default")
      (node (ref "U4") (pin "8") (pinfunction "OUT#_8") (pintype "passive+no_connect"))
    )
    (net (code "86") (name "unconnected-(U4-R232-Pad15)") (class "Default")
      (node (ref "U4") (pin "15") (pinfunction "R232_15") (pintype "passive+no_connect"))
    )
    (net (code "87") (name "unconnected-(U4-RI#-Pad11)") (class "Default")
      (node (ref "U4") (pin "11") (pinfunction "RI#_11") (pintype "passive+no_connect"))
    )
    (net (code "88") (name "unconnected-(USB1-DM-Pad2)") (class "Default")
      (node (ref "USB1") (pin "2") (pinfunction "DM_2") (pintype "passive+no_connect"))
    )
    (net (code "89") (name "unconnected-(USB1-DP-Pad3)") (class "Default")
      (node (ref "USB1") (pin "3") (pinfunction "DP_3") (pintype "passive+no_connect"))
    )
  )
)
